# v1_0_EDA.net
KiCad netlist of a schematic drawn in EasyEDA Pro
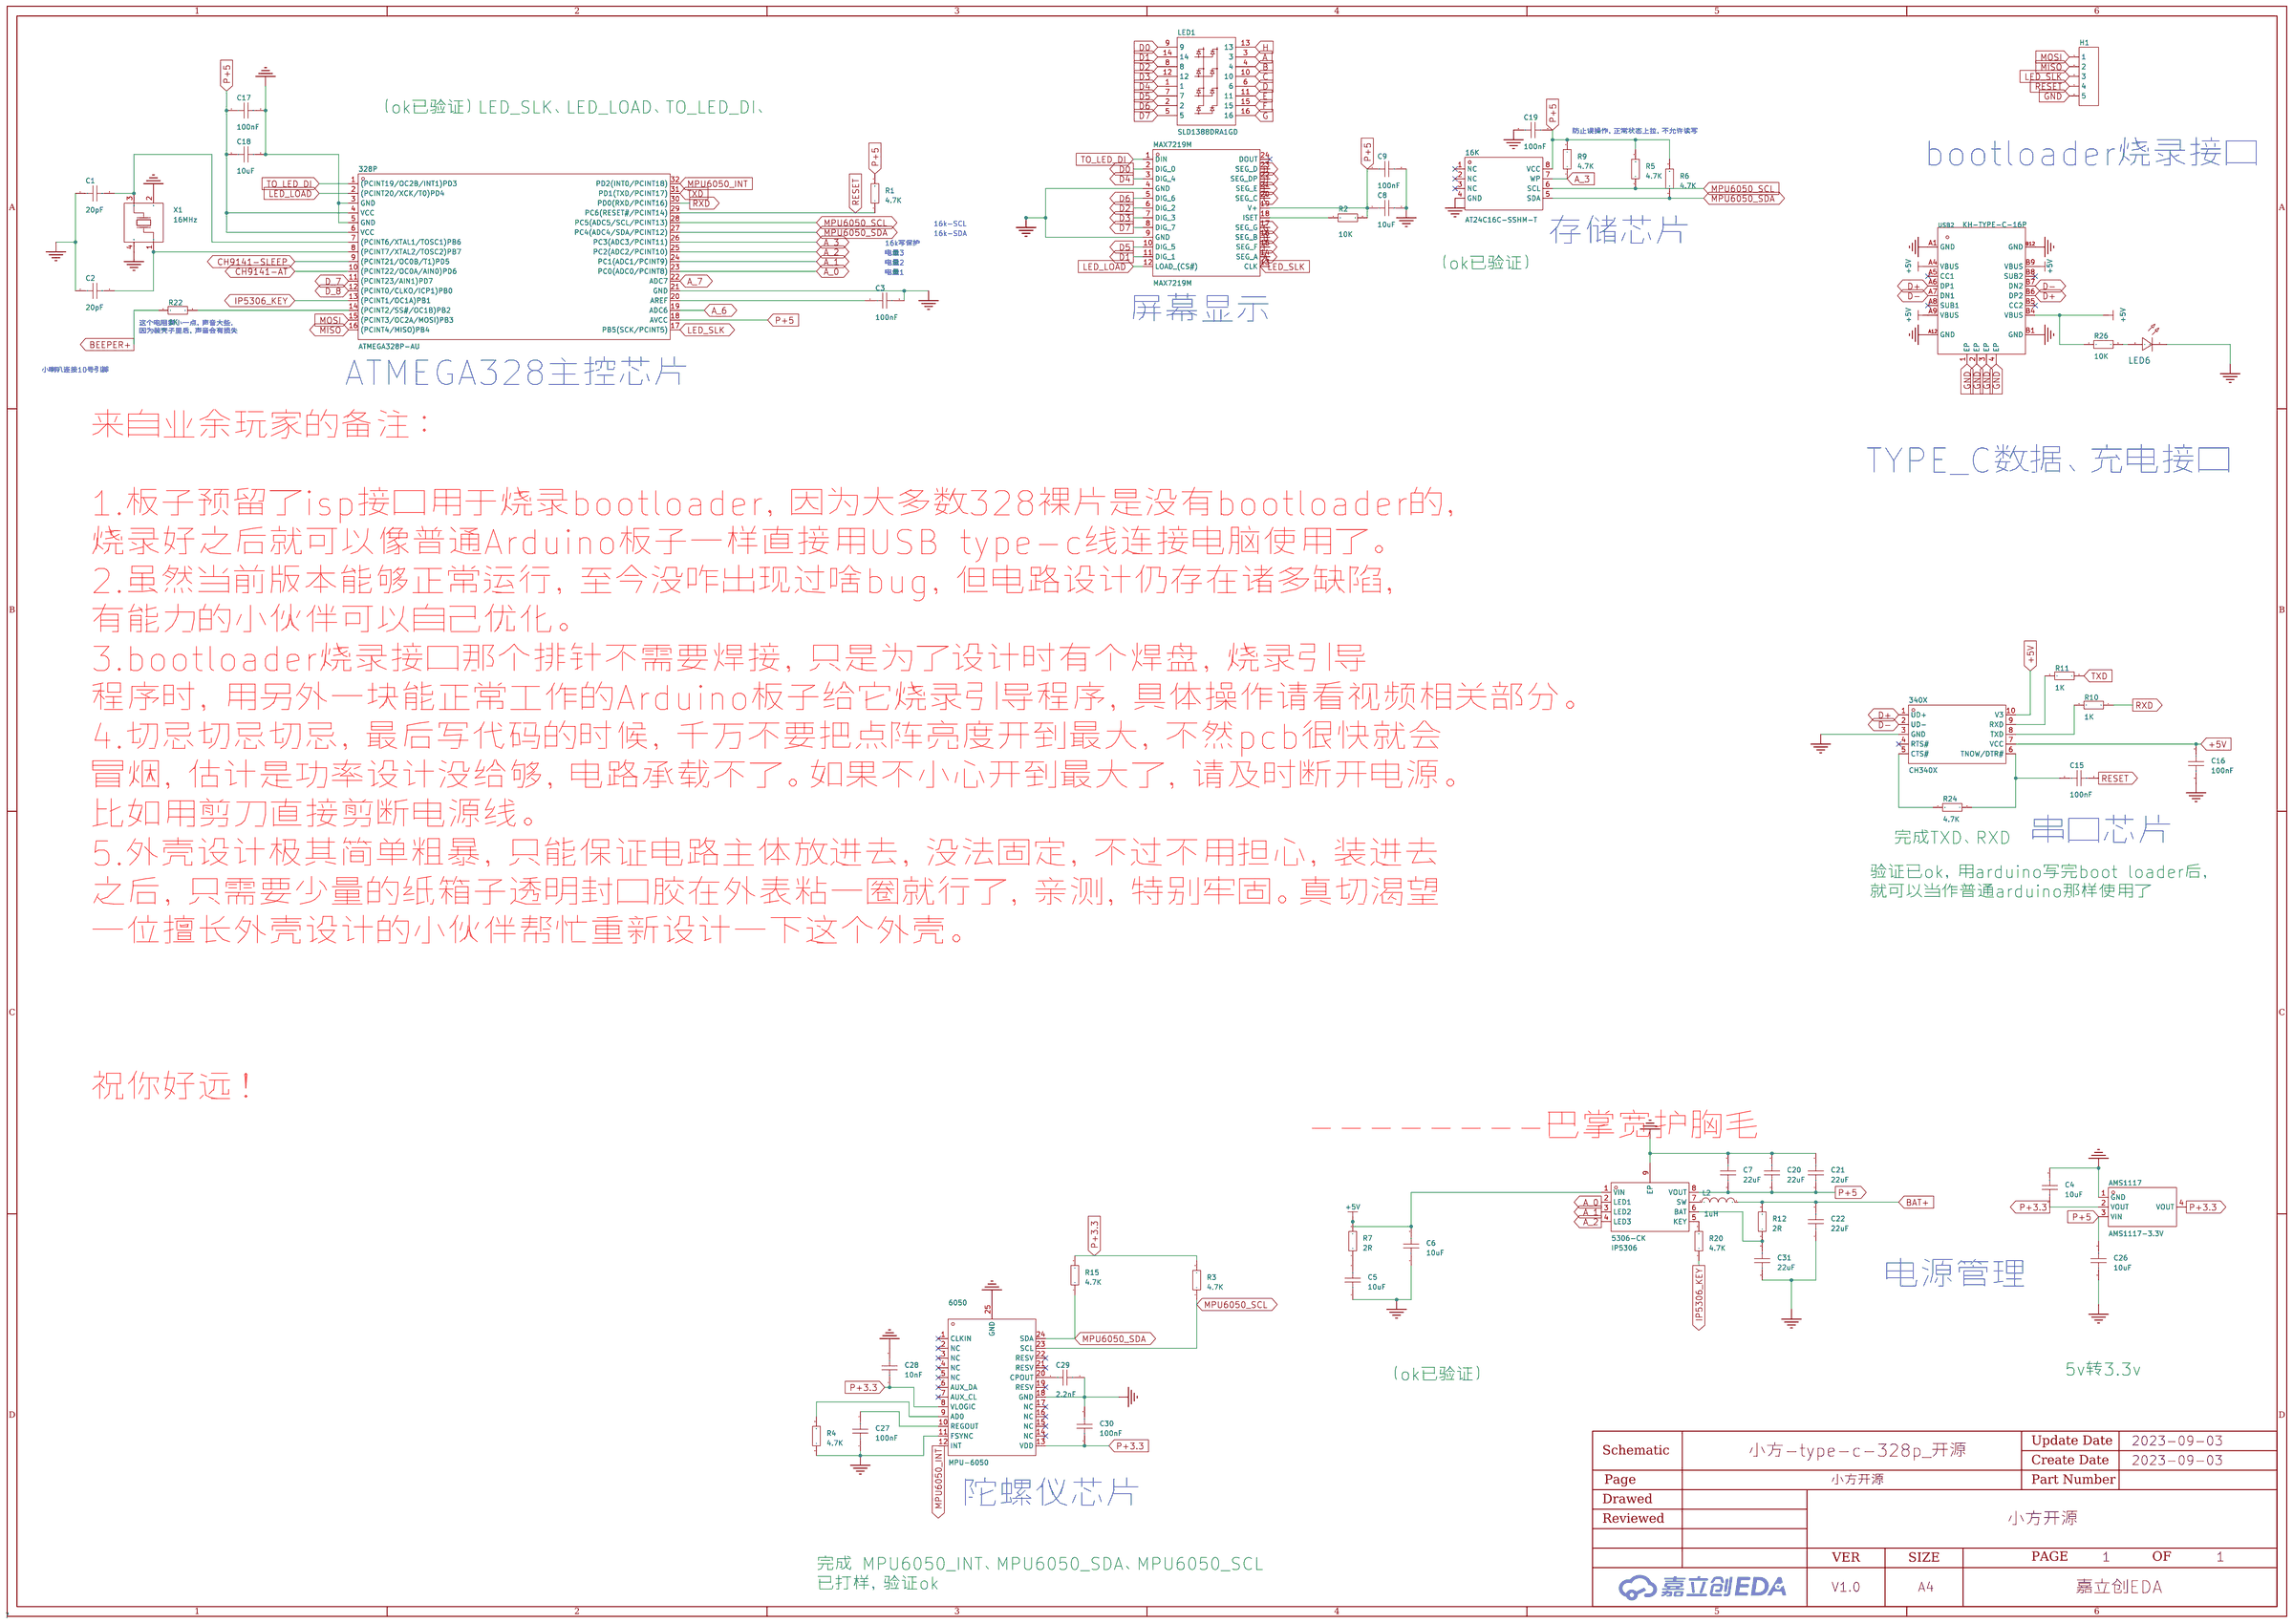
[diagram p0: schematic sheet]

(export (version "E")
  (design (tool "Eeschema 10.0.6"))
  (components
    (comp (ref "16K")
      (value "AT24C16C-SSHM-T")
      (footprint "easyedapro:SOIC-8_L4.9-W3.9-P1.27-LS6.0-BL")
      (fields (field (name "Manufacturer") "MICROCHIP(美国微芯)"))
      (libsource (lib "easyedapro") (part "AT24C16C-SSHM-T"))
    )
    (comp (ref "328P")
      (value "ATMEGA328P-AU")
      (footprint "easyedapro:TQFP-32_L7.0-W7.0-P0.80-LS9.0-BL")
      (fields (field (name "Manufacturer") "MICROCHIP(美国微芯)"))
      (libsource (lib "easyedapro") (part "ATMEGA328P-AU_C3225551"))
    )
    (comp (ref "340X")
      (value "CH340X")
      (footprint "easyedapro:MSOP-10_L3.0-W3.0-P0.50-LS5.0-BL")
      (fields (field (name "Manufacturer") "WCH(南京沁恒)"))
      (libsource (lib "easyedapro") (part "CH340X"))
    )
    (comp (ref "5306-CK")
      (value "IP5306")
      (footprint "easyedapro:ESOP-8_L4.9-W3.9-P1.27-LS6.0-BL-EP")
      (description "2.1A充电2.4A放电高集成度移动电源SOC")
      (fields (field (name "Manufacturer") "INJOINIC(英集芯)"))
      (libsource (lib "easyedapro") (part "IP5306"))
    )
    (comp (ref "6050")
      (value "MPU-6050")
      (footprint "easyedapro:QFN-24_L4.0-W4.0-P0.50-BL-EP2.7")
      (description "三轴加速度计和三轴陀螺仪，工作电压：2.375V~3.46V")
      (fields (field (name "Manufacturer") "TDK InvenSense(应美盛)"))
      (libsource (lib "easyedapro") (part "MPU-6050_C24112"))
    )
    (comp (ref "AMS1117")
      (value "AMS1117-3.3V")
      (footprint "easyedapro:SOT-223_L6.5-W3.5-P2.30-LS7.0-BR")
      (description "输出类型:固定;输出极性:正;输出通道数:1;最大输入电压:12V;输出电压:3.3V;压差:1.5V@(700mA);输出电流:800mA;电源纹波抑制比(PSRR):75dB@(10kHz);")
      (fields (field (name "Manufacturer") "FM(富满)"))
      (libsource (lib "easyedapro") (part "SC1117-3.3V"))
    )
    (comp (ref "C1")
      (value "20pF")
      (footprint "easyedapro:C0603")
      (libsource (lib "easyedapro") (part "CapAcitance"))
    )
    (comp (ref "C2")
      (value "20pF")
      (footprint "easyedapro:C0603")
      (libsource (lib "easyedapro") (part "CapAcitance"))
    )
    (comp (ref "C3")
      (value "100nF")
      (footprint "easyedapro:C0603")
      (libsource (lib "easyedapro") (part "CapAcitance"))
    )
    (comp (ref "C4")
      (value "10uF")
      (footprint "easyedapro:C0603")
      (libsource (lib "easyedapro") (part "CapAcitance"))
    )
    (comp (ref "C5")
      (value "10uF")
      (footprint "easyedapro:C0603")
      (libsource (lib "easyedapro") (part "CapAcitance"))
    )
    (comp (ref "C6")
      (value "10uF")
      (footprint "easyedapro:C0603")
      (libsource (lib "easyedapro") (part "CapAcitance"))
    )
    (comp (ref "C7")
      (value "22uF")
      (footprint "easyedapro:C0603")
      (libsource (lib "easyedapro") (part "CapAcitance"))
    )
    (comp (ref "C8")
      (value "10uF")
      (footprint "easyedapro:C0603")
      (libsource (lib "easyedapro") (part "CapAcitance"))
    )
    (comp (ref "C9")
      (value "100nF")
      (footprint "easyedapro:C0603")
      (libsource (lib "easyedapro") (part "CapAcitance"))
    )
    (comp (ref "C15")
      (value "100nF")
      (footprint "easyedapro:C0603")
      (libsource (lib "easyedapro") (part "CapAcitance"))
    )
    (comp (ref "C16")
      (value "100nF")
      (footprint "easyedapro:C0603")
      (libsource (lib "easyedapro") (part "CapAcitance"))
    )
    (comp (ref "C17")
      (value "100nF")
      (footprint "easyedapro:C0603")
      (libsource (lib "easyedapro") (part "CapAcitance"))
    )
    (comp (ref "C18")
      (value "10uF")
      (footprint "easyedapro:C0603")
      (libsource (lib "easyedapro") (part "CapAcitance"))
    )
    (comp (ref "C19")
      (value "100nF")
      (footprint "easyedapro:C0603")
      (libsource (lib "easyedapro") (part "CapAcitance"))
    )
    (comp (ref "C20")
      (value "22uF")
      (footprint "easyedapro:C0603")
      (libsource (lib "easyedapro") (part "CapAcitance"))
    )
    (comp (ref "C21")
      (value "22uF")
      (footprint "easyedapro:C0603")
      (libsource (lib "easyedapro") (part "CapAcitance"))
    )
    (comp (ref "C22")
      (value "22uF")
      (footprint "easyedapro:C0603")
      (libsource (lib "easyedapro") (part "CapAcitance"))
    )
    (comp (ref "C26")
      (value "10uF")
      (footprint "easyedapro:C0603")
      (libsource (lib "easyedapro") (part "CapAcitance"))
    )
    (comp (ref "C27")
      (value "100nF")
      (footprint "easyedapro:C0603")
      (libsource (lib "easyedapro") (part "CapAcitance"))
    )
    (comp (ref "C28")
      (value "10nF")
      (footprint "easyedapro:C0603")
      (libsource (lib "easyedapro") (part "CapAcitance"))
    )
    (comp (ref "C29")
      (value "2.2nF")
      (footprint "easyedapro:C0603")
      (libsource (lib "easyedapro") (part "CapAcitance"))
    )
    (comp (ref "C30")
      (value "100nF")
      (footprint "easyedapro:C0603")
      (libsource (lib "easyedapro") (part "CapAcitance"))
    )
    (comp (ref "C31")
      (value "22uF")
      (footprint "easyedapro:C0603")
      (libsource (lib "easyedapro") (part "CapAcitance"))
    )
    (comp (ref "H1")
      (value "~")
      (footprint "easyedapro:HDR-TH_5P-P2.54-V-F")
      (libsource (lib "easyedapro") (part "Header-Female-2.54_1x5"))
    )
    (comp (ref "L2")
      (value "1uH")
      (footprint "easyedapro:L0603")
      (libsource (lib "easyedapro") (part "SDFL1608S100KTF"))
    )
    (comp (ref "LED1")
      (value "SLD1388DRA1GD")
      (footprint "easyedapro:LED-TH_SLD1388DRA1GD")
      (description "位数:8x8;发光颜色:红色;极性:共阳;")
      (fields (field (name "Manufacturer") "SUNLIGHT(光华)"))
      (libsource (lib "easyedapro") (part "SLD1388DRA1GD_C2913075"))
    )
    (comp (ref "LED6")
      (value "~")
      (footprint "easyedapro:LED_0603")
      (libsource (lib "easyedapro") (part "LED_R"))
    )
    (comp (ref "MAX7219M")
      (value "MAX7219M")
      (footprint "easyedapro:SOP-24_L15.2-W7.8-P1.27-LS10.6-BL")
      (fields (field (name "Manufacturer") "HGSEMI(华冠)"))
      (libsource (lib "easyedapro") (part "MAX7219M"))
    )
    (comp (ref "R1") (value "4.7K") (footprint "easyedapro:R0603") (libsource (lib "easyedapro") (part "电阻")))
    (comp (ref "R2") (value "10K") (footprint "easyedapro:R0603") (libsource (lib "easyedapro") (part "电阻")))
    (comp (ref "R3") (value "4.7K") (footprint "easyedapro:R0603") (libsource (lib "easyedapro") (part "电阻")))
    (comp (ref "R4") (value "4.7K") (footprint "easyedapro:R0603") (libsource (lib "easyedapro") (part "电阻")))
    (comp (ref "R5") (value "4.7K") (footprint "easyedapro:R0603") (libsource (lib "easyedapro") (part "电阻")))
    (comp (ref "R6") (value "4.7K") (footprint "easyedapro:R0603") (libsource (lib "easyedapro") (part "电阻")))
    (comp (ref "R7") (value "2R") (footprint "easyedapro:R0603") (libsource (lib "easyedapro") (part "电阻")))
    (comp (ref "R9") (value "4.7K") (footprint "easyedapro:R0603") (libsource (lib "easyedapro") (part "电阻")))
    (comp (ref "R10") (value "1K") (footprint "easyedapro:R0603") (libsource (lib "easyedapro") (part "电阻")))
    (comp (ref "R11") (value "1K") (footprint "easyedapro:R0603") (libsource (lib "easyedapro") (part "电阻")))
    (comp (ref "R12") (value "2R") (footprint "easyedapro:R0603") (libsource (lib "easyedapro") (part "电阻")))
    (comp (ref "R15")
      (value "4.7K")
      (footprint "easyedapro:R0603")
      (libsource (lib "easyedapro") (part "电阻"))
    )
    (comp (ref "R20")
      (value "4.7K")
      (footprint "easyedapro:R0603")
      (libsource (lib "easyedapro") (part "电阻"))
    )
    (comp (ref "R22") (value "1K") (footprint "easyedapro:R0603") (libsource (lib "easyedapro") (part "电阻")))
    (comp (ref "R24")
      (value "4.7K")
      (footprint "easyedapro:R0603")
      (libsource (lib "easyedapro") (part "电阻"))
    )
    (comp (ref "R26") (value "10K") (footprint "easyedapro:R0603") (libsource (lib "easyedapro") (part "电阻")))
    (comp (ref "USB2")
      (value "KH-TYPE-C-16P")
      (footprint "easyedapro:USB-C-SMD_KH-TYPE-C-16P")
      (description "Type-C母座 16PIN 立式四角贴板无压片")
      (fields (field (name "Manufacturer") "kinghelm(金航标)"))
      (libsource (lib "easyedapro") (part "KH-TYPE-C-16P"))
    )
    (comp (ref "X1")
      (value "16MHz")
      (footprint "easyedapro:OSC-SMD_4P-L3.2-W2.5-BL")
      (description "晶振类型:贴片无源晶振;频率:16MHz;频率公差:±10ppm;频率稳定度:±30ppm;负载电容:9pF;工作温度:-40°C~+85°C;")
      (fields (field (name "Manufacturer Part") "X322516MLB4SI") (field (name "Manufacturer") "YXC(扬兴晶振)"))
      (libsource (lib "easyedapro") (part "X322516MLB4SI"))
    )
  )
  (nets
    (net (code "1") (name "+5V") (class "Default")
      (node (ref "340X") (pin "10") (pinfunction "V3_10") (pintype "input"))
      (node (ref "340X") (pin "7") (pinfunction "VCC_7") (pintype "input"))
      (node (ref "5306-CK") (pin "1") (pinfunction "VIN_1") (pintype "input"))
      (node (ref "C16") (pin "2") (pinfunction "2_2") (pintype "input"))
      (node (ref "C6") (pin "2") (pinfunction "2_2") (pintype "input"))
      (node (ref "R26") (pin "1") (pinfunction "1_1") (pintype "input"))
      (node (ref "R7") (pin "2") (pinfunction "2_2") (pintype "input"))
      (node (ref "USB2") (pin "A4") (pinfunction "VBUS_A4") (pintype "input"))
      (node (ref "USB2") (pin "A9") (pinfunction "VBUS_A9") (pintype "input"))
      (node (ref "USB2") (pin "B4") (pinfunction "VBUS_B4") (pintype "input"))
      (node (ref "USB2") (pin "B9") (pinfunction "VBUS_B9") (pintype "input"))
    )
    (net (code "2") (name "A") (class "Default")
      (node (ref "LED1") (pin "3") (pinfunction "3_3") (pintype "input"))
      (node (ref "MAX7219M") (pin "14") (pinfunction "SEG_A_14") (pintype "input"))
    )
    (net (code "3") (name "A_0") (class "Default")
      (node (ref "328P") (pin "23") (pinfunction "PC0(ADC0/PCINT8)_23") (pintype "input"))
      (node (ref "5306-CK") (pin "2") (pinfunction "LED1_2") (pintype "input"))
    )
    (net (code "4") (name "A_1") (class "Default")
      (node (ref "328P") (pin "24") (pinfunction "PC1(ADC1/PCINT9)_24") (pintype "input"))
      (node (ref "5306-CK") (pin "3") (pinfunction "LED2_3") (pintype "input"))
    )
    (net (code "5") (name "A_2") (class "Default")
      (node (ref "328P") (pin "25") (pinfunction "PC2(ADC2/PCINT10)_25") (pintype "input"))
      (node (ref "5306-CK") (pin "4") (pinfunction "LED3_4") (pintype "input"))
    )
    (net (code "6") (name "A_3") (class "Default")
      (node (ref "16K") (pin "7") (pinfunction "WP_7") (pintype "input"))
      (node (ref "328P") (pin "26") (pinfunction "PC3(ADC3/PCINT11)_26") (pintype "input"))
      (node (ref "R9") (pin "1") (pinfunction "1_1") (pintype "input"))
    )
    (net (code "7") (name "A_6") (class "Default")
      (node (ref "328P") (pin "19") (pinfunction "ADC6_19") (pintype "input"))
    )
    (net (code "8") (name "A_7") (class "Default")
      (node (ref "328P") (pin "22") (pinfunction "ADC7_22") (pintype "input"))
    )
    (net (code "9") (name "B") (class "Default")
      (node (ref "LED1") (pin "4") (pinfunction "4_4") (pintype "input"))
      (node (ref "MAX7219M") (pin "16") (pinfunction "SEG_B_16") (pintype "input"))
    )
    (net (code "10") (name "BAT+") (class "Default")
      (node (ref "C22") (pin "2") (pinfunction "2_2") (pintype "input"))
      (node (ref "L2") (pin "2") (pinfunction "2_2") (pintype "input"))
      (node (ref "R12") (pin "2") (pinfunction "2_2") (pintype "input"))
    )
    (net (code "11") (name "BEEPER+") (class "Default")
      (node (ref "R22") (pin "1") (pinfunction "1_1") (pintype "input"))
    )
    (net (code "12") (name "C") (class "Default")
      (node (ref "LED1") (pin "10") (pinfunction "10_10") (pintype "input"))
      (node (ref "MAX7219M") (pin "20") (pinfunction "SEG_C_20") (pintype "input"))
    )
    (net (code "13") (name "CH9141-AT") (class "Default")
      (node (ref "328P") (pin "10") (pinfunction "(PCINT22/OC0A/AIN0)PD6_10") (pintype "input"))
    )
    (net (code "14") (name "CH9141-SLEEP") (class "Default")
      (node (ref "328P") (pin "9") (pinfunction "(PCINT21/OC0B/T1)PD5_9") (pintype "input"))
    )
    (net (code "15") (name "D") (class "Default")
      (node (ref "LED1") (pin "6") (pinfunction "6_6") (pintype "input"))
      (node (ref "MAX7219M") (pin "23") (pinfunction "SEG_D_23") (pintype "input"))
    )
    (net (code "16") (name "D+") (class "Default")
      (node (ref "340X") (pin "1") (pinfunction "UD+_1") (pintype "input"))
      (node (ref "USB2") (pin "A6") (pinfunction "DP1_A6") (pintype "input"))
      (node (ref "USB2") (pin "B6") (pinfunction "DP2_B6") (pintype "input"))
    )
    (net (code "17") (name "D-") (class "Default")
      (node (ref "340X") (pin "2") (pinfunction "UD-_2") (pintype "input"))
      (node (ref "USB2") (pin "A7") (pinfunction "DN1_A7") (pintype "input"))
      (node (ref "USB2") (pin "B7") (pinfunction "DN2_B7") (pintype "input"))
    )
    (net (code "18") (name "D0") (class "Default")
      (node (ref "LED1") (pin "9") (pinfunction "9_9") (pintype "input"))
      (node (ref "MAX7219M") (pin "2") (pinfunction "DIG_0_2") (pintype "input"))
    )
    (net (code "19") (name "D1") (class "Default")
      (node (ref "LED1") (pin "14") (pinfunction "14_14") (pintype "input"))
      (node (ref "MAX7219M") (pin "11") (pinfunction "DIG_1_11") (pintype "input"))
    )
    (net (code "20") (name "D2") (class "Default")
      (node (ref "LED1") (pin "8") (pinfunction "8_8") (pintype "input"))
      (node (ref "MAX7219M") (pin "6") (pinfunction "DIG_2_6") (pintype "input"))
    )
    (net (code "21") (name "D3") (class "Default")
      (node (ref "LED1") (pin "12") (pinfunction "12_12") (pintype "input"))
      (node (ref "MAX7219M") (pin "7") (pinfunction "DIG_3_7") (pintype "input"))
    )
    (net (code "22") (name "D4") (class "Default")
      (node (ref "LED1") (pin "1") (pinfunction "1_1") (pintype "input"))
      (node (ref "MAX7219M") (pin "3") (pinfunction "DIG_4_3") (pintype "input"))
    )
    (net (code "23") (name "D5") (class "Default")
      (node (ref "LED1") (pin "7") (pinfunction "7_7") (pintype "input"))
      (node (ref "MAX7219M") (pin "10") (pinfunction "DIG_5_10") (pintype "input"))
    )
    (net (code "24") (name "D6") (class "Default")
      (node (ref "LED1") (pin "2") (pinfunction "2_2") (pintype "input"))
      (node (ref "MAX7219M") (pin "5") (pinfunction "DIG_6_5") (pintype "input"))
    )
    (net (code "25") (name "D7") (class "Default")
      (node (ref "LED1") (pin "5") (pinfunction "5_5") (pintype "input"))
      (node (ref "MAX7219M") (pin "8") (pinfunction "DIG_7_8") (pintype "input"))
    )
    (net (code "26") (name "D_7") (class "Default")
      (node (ref "328P") (pin "11") (pinfunction "(PCINT23/AIN1)PD7_11") (pintype "input"))
    )
    (net (code "27") (name "D_8") (class "Default")
      (node (ref "328P") (pin "12") (pinfunction "(PCINT0/CLKO/ICP1)PB0_12") (pintype "input"))
    )
    (net (code "28") (name "E") (class "Default")
      (node (ref "LED1") (pin "11") (pinfunction "11_11") (pintype "input"))
      (node (ref "MAX7219M") (pin "21") (pinfunction "SEG_E_21") (pintype "input"))
    )
    (net (code "29") (name "F") (class "Default")
      (node (ref "LED1") (pin "15") (pinfunction "15_15") (pintype "input"))
      (node (ref "MAX7219M") (pin "15") (pinfunction "SEG_F_15") (pintype "input"))
    )
    (net (code "30") (name "G") (class "Default")
      (node (ref "LED1") (pin "16") (pinfunction "16_16") (pintype "input"))
      (node (ref "MAX7219M") (pin "17") (pinfunction "SEG_G_17") (pintype "input"))
    )
    (net (code "31") (name "GND") (class "Default")
      (node (ref "16K") (pin "4") (pinfunction "GND_4") (pintype "input"))
      (node (ref "328P") (pin "21") (pinfunction "GND_21") (pintype "input"))
      (node (ref "328P") (pin "3") (pinfunction "GND_3") (pintype "input"))
      (node (ref "328P") (pin "5") (pinfunction "GND_5") (pintype "input"))
      (node (ref "340X") (pin "3") (pinfunction "GND_3") (pintype "input"))
      (node (ref "5306-CK") (pin "9") (pinfunction "EP_9") (pintype "input"))
      (node (ref "6050") (pin "11") (pinfunction "FSYNC_11") (pintype "input"))
      (node (ref "6050") (pin "18") (pinfunction "GND_18") (pintype "input"))
      (node (ref "6050") (pin "25") (pinfunction "GND_25") (pintype "input"))
      (node (ref "AMS1117") (pin "1") (pinfunction "GND_1") (pintype "input"))
      (node (ref "C1") (pin "1") (pinfunction "1_1") (pintype "input"))
      (node (ref "C16") (pin "1") (pinfunction "1_1") (pintype "input"))
      (node (ref "C17") (pin "2") (pinfunction "2_2") (pintype "input"))
      (node (ref "C18") (pin "2") (pinfunction "2_2") (pintype "input"))
      (node (ref "C19") (pin "1") (pinfunction "1_1") (pintype "input"))
      (node (ref "C2") (pin "1") (pinfunction "1_1") (pintype "input"))
      (node (ref "C20") (pin "2") (pinfunction "2_2") (pintype "input"))
      (node (ref "C21") (pin "2") (pinfunction "2_2") (pintype "input"))
      (node (ref "C22") (pin "1") (pinfunction "1_1") (pintype "input"))
      (node (ref "C26") (pin "1") (pinfunction "1_1") (pintype "input"))
      (node (ref "C27") (pin "1") (pinfunction "1_1") (pintype "input"))
      (node (ref "C28") (pin "2") (pinfunction "2_2") (pintype "input"))
      (node (ref "C29") (pin "2") (pinfunction "2_2") (pintype "input"))
      (node (ref "C3") (pin "2") (pinfunction "2_2") (pintype "input"))
      (node (ref "C30") (pin "2") (pinfunction "2_2") (pintype "input"))
      (node (ref "C31") (pin "1") (pinfunction "1_1") (pintype "input"))
      (node (ref "C4") (pin "2") (pinfunction "2_2") (pintype "input"))
      (node (ref "C5") (pin "1") (pinfunction "1_1") (pintype "input"))
      (node (ref "C6") (pin "1") (pinfunction "1_1") (pintype "input"))
      (node (ref "C7") (pin "2") (pinfunction "2_2") (pintype "input"))
      (node (ref "C8") (pin "2") (pinfunction "2_2") (pintype "input"))
      (node (ref "C9") (pin "2") (pinfunction "2_2") (pintype "input"))
      (node (ref "H1") (pin "5") (pinfunction "5_5") (pintype "input"))
      (node (ref "LED6") (pin "1") (pinfunction "C_1") (pintype "input"))
      (node (ref "MAX7219M") (pin "4") (pinfunction "GND_4") (pintype "input"))
      (node (ref "MAX7219M") (pin "9") (pinfunction "GND_9") (pintype "input"))
      (node (ref "R4") (pin "1") (pinfunction "1_1") (pintype "input"))
      (node (ref "USB2") (pin "1") (pinfunction "EP_1") (pintype "input"))
      (node (ref "USB2") (pin "2") (pinfunction "EP_2") (pintype "input"))
      (node (ref "USB2") (pin "3") (pinfunction "EP_3") (pintype "input"))
      (node (ref "USB2") (pin "4") (pinfunction "EP_4") (pintype "input"))
      (node (ref "USB2") (pin "A1") (pinfunction "GND_A1") (pintype "input"))
      (node (ref "USB2") (pin "A12") (pinfunction "GND_A12") (pintype "input"))
      (node (ref "USB2") (pin "B1") (pinfunction "GND_B1") (pintype "input"))
      (node (ref "USB2") (pin "B12") (pinfunction "GND_B12") (pintype "input"))
      (node (ref "X1") (pin "2") (pinfunction "GND_2") (pintype "input"))
      (node (ref "X1") (pin "4") (pinfunction "GND_4") (pintype "input"))
    )
    (net (code "32") (name "H") (class "Default")
      (node (ref "LED1") (pin "13") (pinfunction "13_13") (pintype "input"))
      (node (ref "MAX7219M") (pin "22") (pinfunction "SEG_DP_22") (pintype "input"))
    )
    (net (code "33") (name "IP5306_KEY") (class "Default")
      (node (ref "328P") (pin "13") (pinfunction "(PCINT1/OC1A)PB1_13") (pintype "input"))
      (node (ref "R20") (pin "1") (pinfunction "1_1") (pintype "input"))
    )
    (net (code "34") (name "LED_LOAD") (class "Default")
      (node (ref "328P") (pin "2") (pinfunction "(PCINT20/XCK/T0)PD4_2") (pintype "input"))
      (node (ref "MAX7219M") (pin "12") (pinfunction "LOAD_(CS#)_12") (pintype "input"))
    )
    (net (code "35") (name "LED_SLK") (class "Default")
      (node (ref "328P") (pin "17") (pinfunction "PB5(SCK/PCINT5)_17") (pintype "input"))
      (node (ref "H1") (pin "3") (pinfunction "3_3") (pintype "input"))
      (node (ref "MAX7219M") (pin "13") (pinfunction "CLK_13") (pintype "input"))
    )
    (net (code "36") (name "MISO") (class "Default")
      (node (ref "328P") (pin "16") (pinfunction "(PCINT4/MISO)PB4_16") (pintype "input"))
      (node (ref "H1") (pin "2") (pinfunction "2_2") (pintype "input"))
    )
    (net (code "37") (name "MOSI") (class "Default")
      (node (ref "328P") (pin "15") (pinfunction "(PCINT3/OC2A/MOSI)PB3_15") (pintype "input"))
      (node (ref "H1") (pin "1") (pinfunction "1_1") (pintype "input"))
    )
    (net (code "38") (name "MPU6050_INT") (class "Default")
      (node (ref "328P") (pin "32") (pinfunction "PD2(INT0/PCINT18)_32") (pintype "input"))
      (node (ref "6050") (pin "12") (pinfunction "INT_12") (pintype "input"))
    )
    (net (code "39") (name "MPU6050_SCL") (class "Default")
      (node (ref "16K") (pin "6") (pinfunction "SCL_6") (pintype "input"))
      (node (ref "328P") (pin "28") (pinfunction "PC5(ADC5/SCL/PCINT13)_28") (pintype "input"))
      (node (ref "6050") (pin "23") (pinfunction "SCL_23") (pintype "input"))
      (node (ref "R3") (pin "1") (pinfunction "1_1") (pintype "input"))
      (node (ref "R5") (pin "1") (pinfunction "1_1") (pintype "input"))
    )
    (net (code "40") (name "MPU6050_SDA") (class "Default")
      (node (ref "16K") (pin "5") (pinfunction "SDA_5") (pintype "input"))
      (node (ref "328P") (pin "27") (pinfunction "PC4(ADC4/SDA/PCINT12)_27") (pintype "input"))
      (node (ref "6050") (pin "24") (pinfunction "SDA_24") (pintype "input"))
      (node (ref "R15") (pin "1") (pinfunction "1_1") (pintype "input"))
      (node (ref "R6") (pin "1") (pinfunction "1_1") (pintype "input"))
    )
    (net (code "41") (name "Net-(328P-(PCINT2{slash}SS#{slash}OC1B)PB2)") (class "Default")
      (node (ref "328P") (pin "14") (pinfunction "(PCINT2/SS#/OC1B)PB2_14") (pintype "input"))
      (node (ref "R22") (pin "2") (pinfunction "2_2") (pintype "input"))
    )
    (net (code "42") (name "Net-(328P-(PCINT6{slash}XTAL1{slash}TOSC1)PB6)") (class "Default")
      (node (ref "328P") (pin "7") (pinfunction "(PCINT6/XTAL1/TOSC1)PB6_7") (pintype "input"))
      (node (ref "C1") (pin "2") (pinfunction "2_2") (pintype "input"))
      (node (ref "X1") (pin "3") (pinfunction "OSC2_3") (pintype "input"))
    )
    (net (code "43") (name "Net-(328P-(PCINT7{slash}XTAL2{slash}TOSC2)PB7)") (class "Default")
      (node (ref "328P") (pin "8") (pinfunction "(PCINT7/XTAL2/TOSC2)PB7_8") (pintype "input"))
      (node (ref "C2") (pin "2") (pinfunction "2_2") (pintype "input"))
      (node (ref "X1") (pin "1") (pinfunction "OSC1_1") (pintype "input"))
    )
    (net (code "44") (name "Net-(328P-AREF)") (class "Default")
      (node (ref "328P") (pin "20") (pinfunction "AREF_20") (pintype "input"))
      (node (ref "C3") (pin "1") (pinfunction "1_1") (pintype "input"))
    )
    (net (code "45") (name "Net-(340X-CTS#)") (class "Default")
      (node (ref "340X") (pin "5") (pinfunction "CTS#_5") (pintype "input"))
      (node (ref "R24") (pin "1") (pinfunction "1_1") (pintype "input"))
    )
    (net (code "46") (name "Net-(340X-RXD)") (class "Default")
      (node (ref "340X") (pin "9") (pinfunction "RXD_9") (pintype "input"))
      (node (ref "R11") (pin "2") (pinfunction "2_2") (pintype "input"))
    )
    (net (code "47") (name "Net-(340X-TNOW{slash}DTR#)") (class "Default")
      (node (ref "340X") (pin "6") (pinfunction "TNOW/DTR#_6") (pintype "input"))
      (node (ref "C15") (pin "1") (pinfunction "1_1") (pintype "input"))
      (node (ref "R24") (pin "2") (pinfunction "2_2") (pintype "input"))
    )
    (net (code "48") (name "Net-(340X-TXD)") (class "Default")
      (node (ref "340X") (pin "8") (pinfunction "TXD_8") (pintype "input"))
      (node (ref "R10") (pin "2") (pinfunction "2_2") (pintype "input"))
    )
    (net (code "49") (name "Net-(5306-CK-BAT)") (class "Default")
      (node (ref "5306-CK") (pin "6") (pinfunction "BAT_6") (pintype "input"))
      (node (ref "C31") (pin "2") (pinfunction "2_2") (pintype "input"))
      (node (ref "R12") (pin "1") (pinfunction "1_1") (pintype "input"))
    )
    (net (code "50") (name "Net-(5306-CK-KEY)") (class "Default")
      (node (ref "5306-CK") (pin "5") (pinfunction "KEY_5") (pintype "input"))
      (node (ref "R20") (pin "2") (pinfunction "2_2") (pintype "input"))
    )
    (net (code "51") (name "Net-(5306-CK-SW)") (class "Default")
      (node (ref "5306-CK") (pin "7") (pinfunction "SW_7") (pintype "input"))
      (node (ref "L2") (pin "1") (pinfunction "1_1") (pintype "input"))
    )
    (net (code "52") (name "Net-(6050-AD0)") (class "Default")
      (node (ref "6050") (pin "9") (pinfunction "AD0_9") (pintype "input"))
      (node (ref "R4") (pin "2") (pinfunction "2_2") (pintype "input"))
    )
    (net (code "53") (name "Net-(6050-CPOUT)") (class "Default")
      (node (ref "6050") (pin "20") (pinfunction "CPOUT_20") (pintype "input"))
      (node (ref "C29") (pin "1") (pinfunction "1_1") (pintype "input"))
    )
    (net (code "54") (name "Net-(6050-REGOUT)") (class "Default")
      (node (ref "6050") (pin "10") (pinfunction "REGOUT_10") (pintype "input"))
      (node (ref "C27") (pin "2") (pinfunction "2_2") (pintype "input"))
    )
    (net (code "55") (name "Net-(C5-Pad2)") (class "Default")
      (node (ref "C5") (pin "2") (pinfunction "2_2") (pintype "input"))
      (node (ref "R7") (pin "1") (pinfunction "1_1") (pintype "input"))
    )
    (net (code "56") (name "Net-(LED6-A)") (class "Default")
      (node (ref "LED6") (pin "2") (pinfunction "A_2") (pintype "input"))
      (node (ref "R26") (pin "2") (pinfunction "2_2") (pintype "input"))
    )
    (net (code "57") (name "Net-(MAX7219M-ISET)") (class "Default")
      (node (ref "MAX7219M") (pin "18") (pinfunction "ISET_18") (pintype "input"))
      (node (ref "R2") (pin "1") (pinfunction "1_1") (pintype "input"))
    )
    (net (code "58") (name "P+3.3") (class "Default")
      (node (ref "6050") (pin "13") (pinfunction "VDD_13") (pintype "input"))
      (node (ref "6050") (pin "8") (pinfunction "VLOGIC_8") (pintype "input"))
      (node (ref "AMS1117") (pin "2") (pinfunction "VOUT_2") (pintype "input"))
      (node (ref "AMS1117") (pin "4") (pinfunction "VOUT_4") (pintype "input"))
      (node (ref "C28") (pin "1") (pinfunction "1_1") (pintype "input"))
      (node (ref "C30") (pin "1") (pinfunction "1_1") (pintype "input"))
      (node (ref "C4") (pin "1") (pinfunction "1_1") (pintype "input"))
      (node (ref "R15") (pin "2") (pinfunction "2_2") (pintype "input"))
      (node (ref "R3") (pin "2") (pinfunction "2_2") (pintype "input"))
    )
    (net (code "59") (name "P+5") (class "Default")
      (node (ref "16K") (pin "8") (pinfunction "VCC_8") (pintype "input"))
      (node (ref "328P") (pin "18") (pinfunction "AVCC_18") (pintype "input"))
      (node (ref "328P") (pin "4") (pinfunction "VCC_4") (pintype "input"))
      (node (ref "328P") (pin "6") (pinfunction "VCC_6") (pintype "input"))
      (node (ref "5306-CK") (pin "8") (pinfunction "VOUT_8") (pintype "input"))
      (node (ref "AMS1117") (pin "3") (pinfunction "VIN_3") (pintype "input"))
      (node (ref "C17") (pin "1") (pinfunction "1_1") (pintype "input"))
      (node (ref "C18") (pin "1") (pinfunction "1_1") (pintype "input"))
      (node (ref "C19") (pin "2") (pinfunction "2_2") (pintype "input"))
      (node (ref "C20") (pin "1") (pinfunction "1_1") (pintype "input"))
      (node (ref "C21") (pin "1") (pinfunction "1_1") (pintype "input"))
      (node (ref "C26") (pin "2") (pinfunction "2_2") (pintype "input"))
      (node (ref "C7") (pin "1") (pinfunction "1_1") (pintype "input"))
      (node (ref "C8") (pin "1") (pinfunction "1_1") (pintype "input"))
      (node (ref "C9") (pin "1") (pinfunction "1_1") (pintype "input"))
      (node (ref "MAX7219M") (pin "19") (pinfunction "V+_19") (pintype "input"))
      (node (ref "R1") (pin "2") (pinfunction "2_2") (pintype "input"))
      (node (ref "R2") (pin "2") (pinfunction "2_2") (pintype "input"))
      (node (ref "R5") (pin "2") (pinfunction "2_2") (pintype "input"))
      (node (ref "R6") (pin "2") (pinfunction "2_2") (pintype "input"))
      (node (ref "R9") (pin "2") (pinfunction "2_2") (pintype "input"))
    )
    (net (code "60") (name "RESET") (class "Default")
      (node (ref "328P") (pin "29") (pinfunction "PC6(RESET#/PCINT14)_29") (pintype "input"))
      (node (ref "C15") (pin "2") (pinfunction "2_2") (pintype "input"))
      (node (ref "H1") (pin "4") (pinfunction "4_4") (pintype "input"))
      (node (ref "R1") (pin "1") (pinfunction "1_1") (pintype "input"))
    )
    (net (code "61") (name "RXD") (class "Default")
      (node (ref "328P") (pin "30") (pinfunction "PD0(RXD/PCINT16)_30") (pintype "input"))
      (node (ref "R10") (pin "1") (pinfunction "1_1") (pintype "input"))
    )
    (net (code "62") (name "TO_LED_DI") (class "Default")
      (node (ref "328P") (pin "1") (pinfunction "(PCINT19/OC2B/INT1)PD3_1") (pintype "input"))
      (node (ref "MAX7219M") (pin "1") (pinfunction "DIN_1") (pintype "input"))
    )
    (net (code "63") (name "TXD") (class "Default")
      (node (ref "328P") (pin "31") (pinfunction "PD1(TXD/PCINT17)_31") (pintype "input"))
      (node (ref "R11") (pin "1") (pinfunction "1_1") (pintype "input"))
    )
    (net (code "64") (name "unconnected-(16K-NC-Pad1)") (class "Default")
      (node (ref "16K") (pin "1") (pinfunction "NC_1") (pintype "input+no_connect"))
    )
    (net (code "65") (name "unconnected-(16K-NC-Pad2)") (class "Default")
      (node (ref "16K") (pin "2") (pinfunction "NC_2") (pintype "input+no_connect"))
    )
    (net (code "66") (name "unconnected-(16K-NC-Pad3)") (class "Default")
      (node (ref "16K") (pin "3") (pinfunction "NC_3") (pintype "input+no_connect"))
    )
    (net (code "67") (name "unconnected-(340X-RTS#-Pad4)") (class "Default")
      (node (ref "340X") (pin "4") (pinfunction "RTS#_4") (pintype "input+no_connect"))
    )
    (net (code "68") (name "unconnected-(6050-AUX_CL-Pad7)") (class "Default")
      (node (ref "6050") (pin "7") (pinfunction "AUX_CL_7") (pintype "input+no_connect"))
    )
    (net (code "69") (name "unconnected-(6050-AUX_DA-Pad6)") (class "Default")
      (node (ref "6050") (pin "6") (pinfunction "AUX_DA_6") (pintype "input+no_connect"))
    )
    (net (code "70") (name "unconnected-(6050-CLKIN-Pad1)") (class "Default")
      (node (ref "6050") (pin "1") (pinfunction "CLKIN_1") (pintype "input+no_connect"))
    )
    (net (code "71") (name "unconnected-(6050-NC-Pad2)") (class "Default")
      (node (ref "6050") (pin "2") (pinfunction "NC_2") (pintype "input+no_connect"))
    )
    (net (code "72") (name "unconnected-(6050-NC-Pad3)") (class "Default")
      (node (ref "6050") (pin "3") (pinfunction "NC_3") (pintype "input+no_connect"))
    )
    (net (code "73") (name "unconnected-(6050-NC-Pad4)") (class "Default")
      (node (ref "6050") (pin "4") (pinfunction "NC_4") (pintype "input+no_connect"))
    )
    (net (code "74") (name "unconnected-(6050-NC-Pad5)") (class "Default")
      (node (ref "6050") (pin "5") (pinfunction "NC_5") (pintype "input+no_connect"))
    )
    (net (code "75") (name "unconnected-(6050-NC-Pad14)") (class "Default")
      (node (ref "6050") (pin "14") (pinfunction "NC_14") (pintype "input+no_connect"))
    )
    (net (code "76") (name "unconnected-(6050-NC-Pad15)") (class "Default")
      (node (ref "6050") (pin "15") (pinfunction "NC_15") (pintype "input+no_connect"))
    )
    (net (code "77") (name "unconnected-(6050-NC-Pad16)") (class "Default")
      (node (ref "6050") (pin "16") (pinfunction "NC_16") (pintype "input+no_connect"))
    )
    (net (code "78") (name "unconnected-(6050-NC-Pad17)") (class "Default")
      (node (ref "6050") (pin "17") (pinfunction "NC_17") (pintype "input+no_connect"))
    )
    (net (code "79") (name "unconnected-(6050-RESV-Pad19)") (class "Default")
      (node (ref "6050") (pin "19") (pinfunction "RESV_19") (pintype "input+no_connect"))
    )
    (net (code "80") (name "unconnected-(6050-RESV-Pad21)") (class "Default")
      (node (ref "6050") (pin "21") (pinfunction "RESV_21") (pintype "input+no_connect"))
    )
    (net (code "81") (name "unconnected-(6050-RESV-Pad22)") (class "Default")
      (node (ref "6050") (pin "22") (pinfunction "RESV_22") (pintype "input+no_connect"))
    )
    (net (code "82") (name "unconnected-(MAX7219M-DOUT-Pad24)") (class "Default")
      (node (ref "MAX7219M") (pin "24") (pinfunction "DOUT_24") (pintype "input+no_connect"))
    )
    (net (code "83") (name "unconnected-(USB2-CC1-PadA5)") (class "Default")
      (node (ref "USB2") (pin "A5") (pinfunction "CC1_A5") (pintype "input+no_connect"))
    )
    (net (code "84") (name "unconnected-(USB2-CC2-PadB5)") (class "Default")
      (node (ref "USB2") (pin "B5") (pinfunction "CC2_B5") (pintype "input+no_connect"))
    )
    (net (code "85") (name "unconnected-(USB2-SUB1-PadA8)") (class "Default")
      (node (ref "USB2") (pin "A8") (pinfunction "SUB1_A8") (pintype "input+no_connect"))
    )
    (net (code "86") (name "unconnected-(USB2-SUB2-PadB8)") (class "Default")
      (node (ref "USB2") (pin "B8") (pinfunction "SUB2_B8") (pintype "input+no_connect"))
    )
  )
)
